# untitled.net
KiCad netlist of a schematic drawn in EAGLE
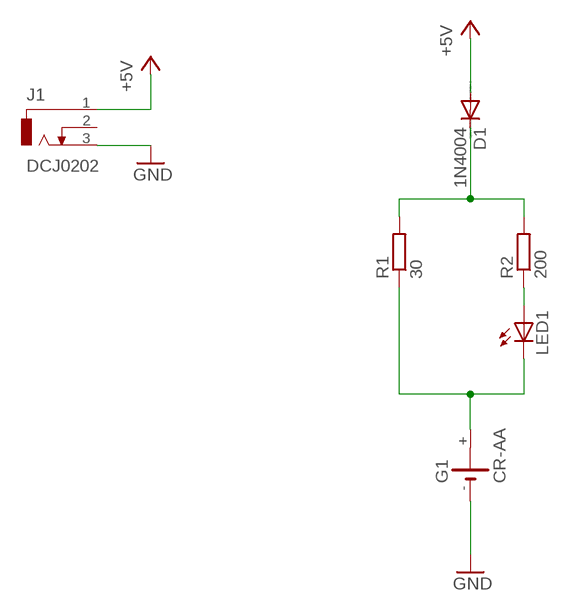
[diagram p0: schematic, sheet 1]

(export (version "E")
  (design (tool "Eeschema 10.0.6"))
  (components
    (comp (ref "D1")
      (value "1N4004")
      (footprint "eagle-import:DO41-10")
      (libsource (lib "eagle-import") (part "1N4004"))
    )
    (comp (ref "G1")
      (value "CR-AA")
      (footprint "eagle-import:CRAA")
      (libsource (lib "eagle-import") (part "CR-AA"))
    )
    (comp (ref "J1")
      (value "DCJ0202")
      (footprint "eagle-import:DCJ0202")
      (libsource (lib "eagle-import") (part "DCJ0202"))
    )
    (comp (ref "LED1")
      (value "LEDCHIP-LED0805")
      (footprint "eagle-import:CHIP-LED0805")
      (libsource (lib "eagle-import") (part "LEDCHIP-LED0805"))
    )
    (comp (ref "R1")
      (value "30")
      (footprint "eagle-import:M1206")
      (libsource (lib "eagle-import") (part "R-EU_M1206"))
    )
    (comp (ref "R2")
      (value "200")
      (footprint "eagle-import:M1206")
      (libsource (lib "eagle-import") (part "R-EU_M1206"))
    )
  )
  (nets
    (net (code "1") (name "+5V") (class "Default")
      (node (ref "D1") (pin "A") (pinfunction "A_A") (pintype "passive"))
      (node (ref "J1") (pin "1") (pinfunction "1_1") (pintype "passive"))
    )
    (net (code "2") (name "GND") (class "Default")
      (node (ref "G1") (pin "-") (pinfunction "-_-") (pintype "passive"))
      (node (ref "J1") (pin "3") (pinfunction "3_3") (pintype "passive"))
    )
    (net (code "3") (name "Net-(D1-PadC)") (class "Default")
      (node (ref "D1") (pin "C") (pinfunction "C_C") (pintype "passive"))
      (node (ref "R1") (pin "2") (pinfunction "2_2") (pintype "passive"))
      (node (ref "R2") (pin "2") (pinfunction "2_2") (pintype "passive"))
    )
    (net (code "4") (name "Net-(G1-Pad+)") (class "Default")
      (node (ref "G1") (pin "+") (pinfunction "+_+") (pintype "passive"))
      (node (ref "LED1") (pin "C") (pinfunction "C_C") (pintype "passive"))
      (node (ref "R1") (pin "1") (pinfunction "1_1") (pintype "passive"))
    )
    (net (code "5") (name "Net-(LED1-PadA)") (class "Default")
      (node (ref "LED1") (pin "A") (pinfunction "A_A") (pintype "passive"))
      (node (ref "R2") (pin "1") (pinfunction "1_1") (pintype "passive"))
    )
    (net (code "6") (name "unconnected-(G1-+-Pad+@1)") (class "Default")
      (node (ref "G1") (pin "+@1") (pinfunction "+_+@1") (pintype "passive"))
    )
    (net (code "7") (name "unconnected-(J1-Pad2)") (class "Default")
      (node (ref "J1") (pin "2") (pinfunction "2_2") (pintype "passive"))
    )
  )
)
